# Serial_final_rev03.net
KiCad netlist of a schematic drawn in EAGLE
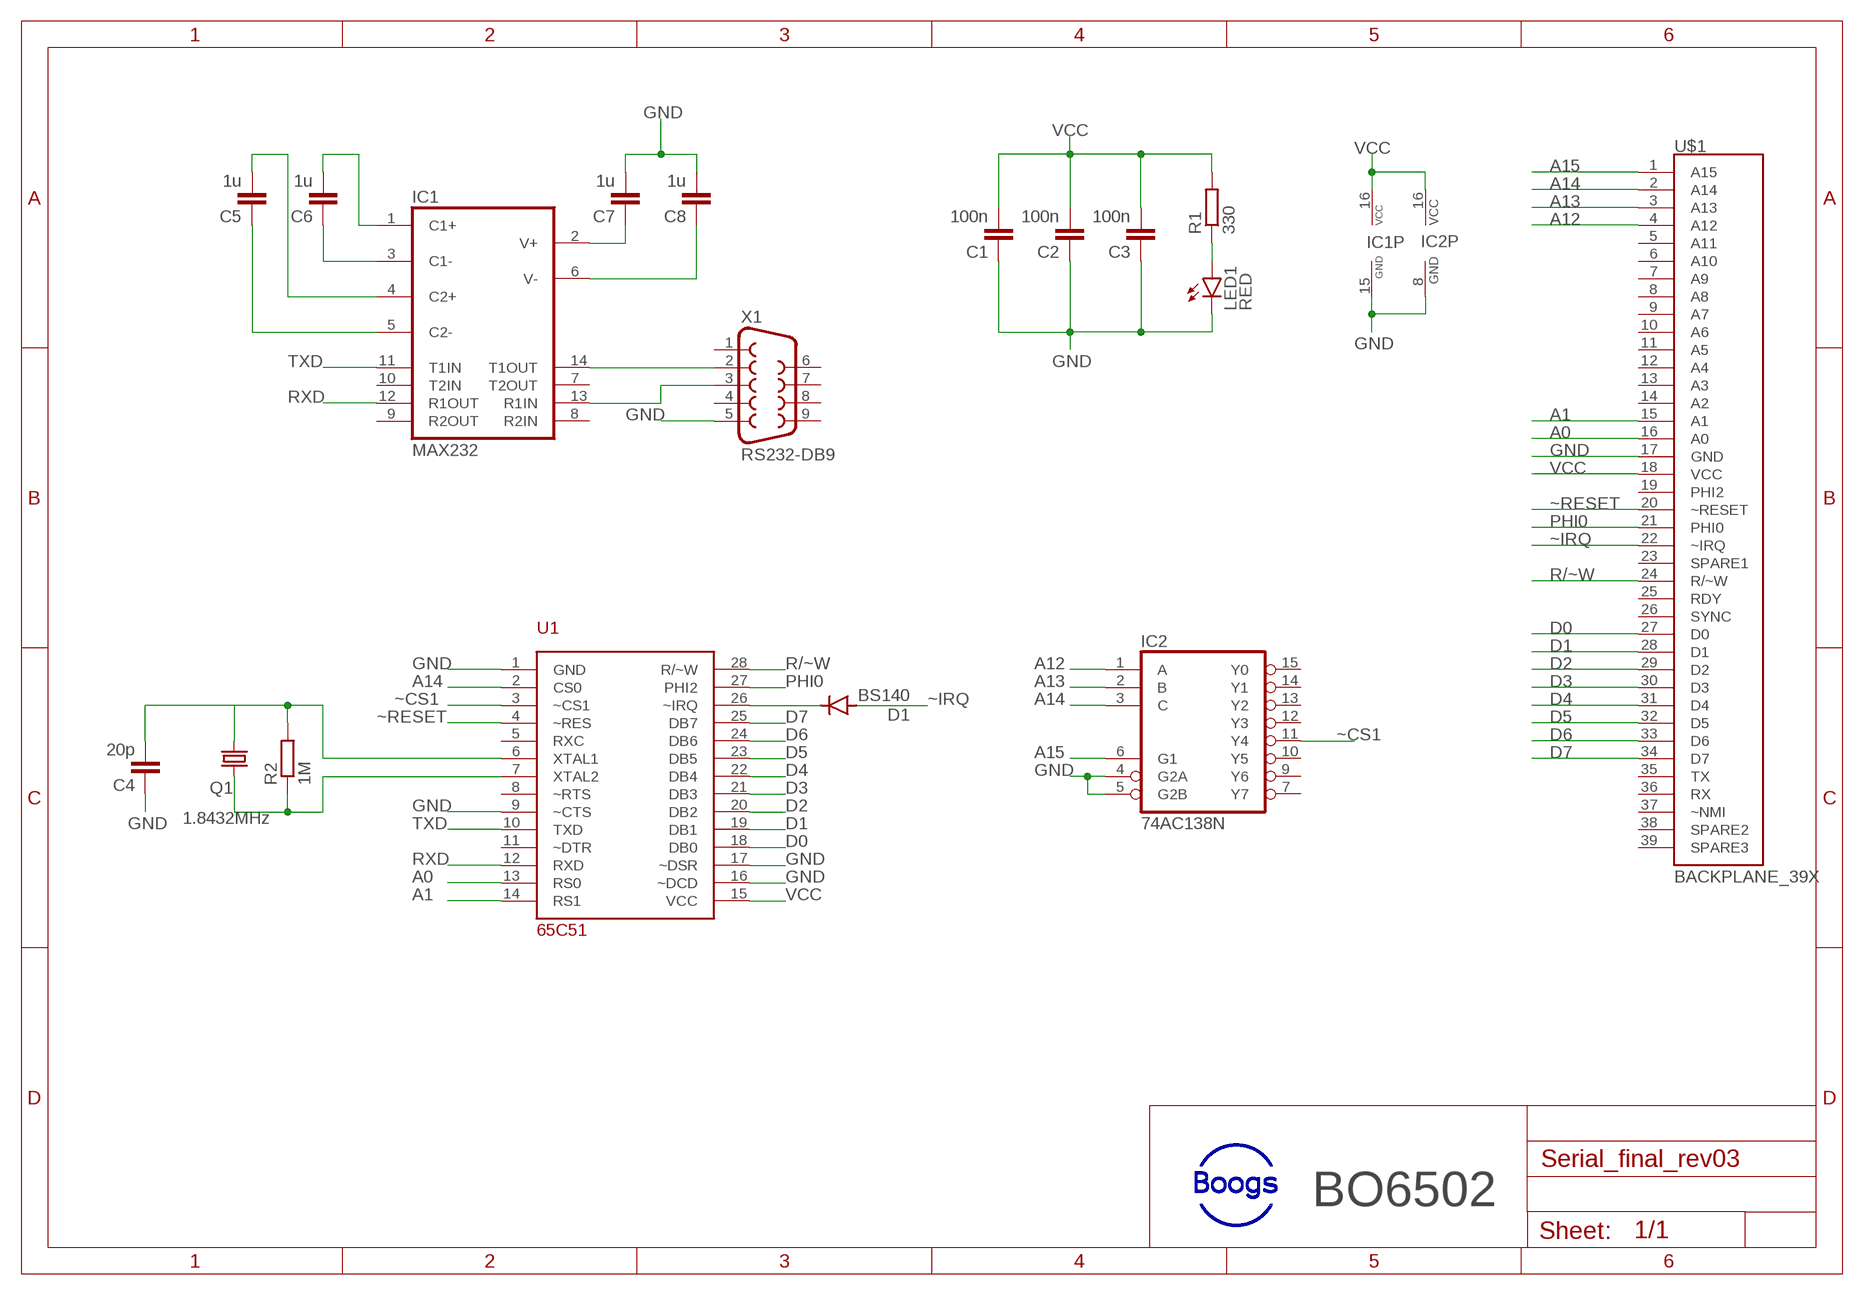
[diagram p0: schematic, sheet 1]

(export (version "E")
  (design (tool "Eeschema 10.0.6"))
  (components
    (comp (ref "C1")
      (value "100n")
      (footprint "eagle-import:C025-025X050")
      (libsource (lib "eagle-import") (part "C-EU025-025X050"))
    )
    (comp (ref "C2")
      (value "100n")
      (footprint "eagle-import:C025-025X050")
      (libsource (lib "eagle-import") (part "C-EU025-025X050"))
    )
    (comp (ref "C3")
      (value "100n")
      (footprint "eagle-import:C025-025X050")
      (libsource (lib "eagle-import") (part "C-EU025-025X050"))
    )
    (comp (ref "C4")
      (value "20p")
      (footprint "eagle-import:C025-025X050")
      (libsource (lib "eagle-import") (part "C-EU025-025X050"))
    )
    (comp (ref "C5")
      (value "1u")
      (footprint "eagle-import:C050-025X075")
      (libsource (lib "eagle-import") (part "C-EU050-025X075"))
    )
    (comp (ref "C6")
      (value "1u")
      (footprint "eagle-import:C050-025X075")
      (libsource (lib "eagle-import") (part "C-EU050-025X075"))
    )
    (comp (ref "C7")
      (value "1u")
      (footprint "eagle-import:C050-025X075")
      (libsource (lib "eagle-import") (part "C-EU050-025X075"))
    )
    (comp (ref "C8")
      (value "1u")
      (footprint "eagle-import:C050-025X075")
      (libsource (lib "eagle-import") (part "C-EU050-025X075"))
    )
    (comp (ref "D1")
      (value "BS140")
      (footprint "eagle-import:DO41-10")
      (libsource (lib "eagle-import") (part "1N4004"))
    )
    (comp (ref "IC1")
      (value "MAX232")
      (footprint "eagle-import:DIL16")
      (fields (field (name "MF") "MAXIM") (field (name "MPN") "MAX232ACPE+"))
      (libsource (lib "eagle-import") (part "MAX232"))
    )
    (comp (ref "IC2")
      (value "74AC138N")
      (footprint "eagle-import:DIL16")
      (libsource (lib "eagle-import") (part "74138NAC"))
    )
    (comp (ref "LED1")
      (value "RED")
      (footprint "eagle-import:LED5MM")
      (libsource (lib "eagle-import") (part "LED5MM"))
    )
    (comp (ref "Q1")
      (value "1.8432MHz")
      (footprint "eagle-import:HC49_S")
      (libsource (lib "eagle-import") (part "CRYSTALHC49S"))
    )
    (comp (ref "R1")
      (value "330")
      (footprint "eagle-import:0207_10")
      (libsource (lib "eagle-import") (part "R-EU_0207/10"))
    )
    (comp (ref "R2")
      (value "1M")
      (footprint "eagle-import:0207_10")
      (libsource (lib "eagle-import") (part "R-EU_0207/10"))
    )
    (comp (ref "U$1")
      (value "BACKPLANE_39X")
      (footprint "eagle-import:BP_39X")
      (fields (field (name "A15") "A15"))
      (libsource (lib "eagle-import") (part "BACKPLANE_39X"))
    )
    (comp (ref "U1")
      (value "65C51")
      (footprint "eagle-import:DIL28")
      (libsource (lib "eagle-import") (part "65C51"))
    )
    (comp (ref "X1")
      (value "RS232-DB9")
      (footprint "eagle-import:F09HP")
      (libsource (lib "eagle-import") (part "F09HP"))
    )
  )
  (nets
    (net (code "1") (name "/A0") (class "Default")
      (node (ref "U$1") (pin "16") (pinfunction "A0_16") (pintype "bidirectional"))
      (node (ref "U1") (pin "13") (pinfunction "RS0_13") (pintype "bidirectional"))
    )
    (net (code "2") (name "/A1") (class "Default")
      (node (ref "U$1") (pin "15") (pinfunction "A1_15") (pintype "bidirectional"))
      (node (ref "U1") (pin "14") (pinfunction "RS1_14") (pintype "bidirectional"))
    )
    (net (code "3") (name "/A12") (class "Default")
      (node (ref "IC2") (pin "1") (pinfunction "A_1") (pintype "input"))
      (node (ref "U$1") (pin "4") (pinfunction "A12_4") (pintype "bidirectional"))
    )
    (net (code "4") (name "/A13") (class "Default")
      (node (ref "IC2") (pin "2") (pinfunction "B_2") (pintype "input"))
      (node (ref "U$1") (pin "3") (pinfunction "A13_3") (pintype "bidirectional"))
    )
    (net (code "5") (name "/A14") (class "Default")
      (node (ref "IC2") (pin "3") (pinfunction "C_3") (pintype "input"))
      (node (ref "U$1") (pin "2") (pinfunction "A14_2") (pintype "bidirectional"))
      (node (ref "U1") (pin "2") (pinfunction "CS0_2") (pintype "bidirectional"))
    )
    (net (code "6") (name "/A15") (class "Default")
      (node (ref "IC2") (pin "6") (pinfunction "G1_6") (pintype "input"))
      (node (ref "U$1") (pin "1") (pinfunction "A15_1") (pintype "bidirectional"))
    )
    (net (code "7") (name "/D0") (class "Default")
      (node (ref "U$1") (pin "27") (pinfunction "D0_27") (pintype "bidirectional"))
      (node (ref "U1") (pin "18") (pinfunction "DB0_18") (pintype "bidirectional"))
    )
    (net (code "8") (name "/D1") (class "Default")
      (node (ref "U$1") (pin "28") (pinfunction "D1_28") (pintype "bidirectional"))
      (node (ref "U1") (pin "19") (pinfunction "DB1_19") (pintype "bidirectional"))
    )
    (net (code "9") (name "/D2") (class "Default")
      (node (ref "U$1") (pin "29") (pinfunction "D2_29") (pintype "bidirectional"))
      (node (ref "U1") (pin "20") (pinfunction "DB2_20") (pintype "bidirectional"))
    )
    (net (code "10") (name "/D3") (class "Default")
      (node (ref "U$1") (pin "30") (pinfunction "D3_30") (pintype "bidirectional"))
      (node (ref "U1") (pin "21") (pinfunction "DB3_21") (pintype "bidirectional"))
    )
    (net (code "11") (name "/D4") (class "Default")
      (node (ref "U$1") (pin "31") (pinfunction "D4_31") (pintype "bidirectional"))
      (node (ref "U1") (pin "22") (pinfunction "DB4_22") (pintype "bidirectional"))
    )
    (net (code "12") (name "/D5") (class "Default")
      (node (ref "U$1") (pin "32") (pinfunction "D5_32") (pintype "bidirectional"))
      (node (ref "U1") (pin "23") (pinfunction "DB5_23") (pintype "bidirectional"))
    )
    (net (code "13") (name "/D6") (class "Default")
      (node (ref "U$1") (pin "33") (pinfunction "D6_33") (pintype "bidirectional"))
      (node (ref "U1") (pin "24") (pinfunction "DB6_24") (pintype "bidirectional"))
    )
    (net (code "14") (name "/D7") (class "Default")
      (node (ref "U$1") (pin "34") (pinfunction "D7_34") (pintype "bidirectional"))
      (node (ref "U1") (pin "25") (pinfunction "DB7_25") (pintype "bidirectional"))
    )
    (net (code "15") (name "/GND") (class "Default")
      (node (ref "C1") (pin "1") (pinfunction "1_1") (pintype "passive"))
      (node (ref "C2") (pin "1") (pinfunction "1_1") (pintype "passive"))
      (node (ref "C3") (pin "1") (pinfunction "1_1") (pintype "passive"))
      (node (ref "C4") (pin "1") (pinfunction "1_1") (pintype "passive"))
      (node (ref "C7") (pin "2") (pinfunction "2_2") (pintype "passive"))
      (node (ref "C8") (pin "2") (pinfunction "2_2") (pintype "passive"))
      (node (ref "IC1") (pin "15") (pinfunction "GND_15") (pintype "power_in"))
      (node (ref "IC2") (pin "4") (pinfunction "G2A_4") (pintype "input"))
      (node (ref "IC2") (pin "5") (pinfunction "G2B_5") (pintype "input"))
      (node (ref "IC2") (pin "8") (pinfunction "GND_8") (pintype "power_in"))
      (node (ref "LED1") (pin "K") (pinfunction "C_K") (pintype "passive"))
      (node (ref "U$1") (pin "17") (pinfunction "GND_17") (pintype "bidirectional"))
      (node (ref "U1") (pin "1") (pinfunction "GND_1") (pintype "bidirectional"))
      (node (ref "U1") (pin "16") (pinfunction "~{DCD}_16") (pintype "bidirectional"))
      (node (ref "U1") (pin "17") (pinfunction "~{DSR}_17") (pintype "bidirectional"))
      (node (ref "U1") (pin "9") (pinfunction "~{CTS}_9") (pintype "bidirectional"))
      (node (ref "X1") (pin "5") (pinfunction "5_5") (pintype "passive"))
    )
    (net (code "16") (name "/PHI0") (class "Default")
      (node (ref "U$1") (pin "21") (pinfunction "PHI0_21") (pintype "bidirectional"))
      (node (ref "U1") (pin "27") (pinfunction "PHI2_27") (pintype "bidirectional"))
    )
    (net (code "17") (name "/RXD") (class "Default")
      (node (ref "IC1") (pin "12") (pinfunction "R1OUT_12") (pintype "output"))
      (node (ref "U1") (pin "12") (pinfunction "RXD_12") (pintype "bidirectional"))
    )
    (net (code "18") (name "/R{slash}~{W}") (class "Default")
      (node (ref "U$1") (pin "24") (pinfunction "R/~{W}_24") (pintype "bidirectional"))
      (node (ref "U1") (pin "28") (pinfunction "R/~{W}_28") (pintype "bidirectional"))
    )
    (net (code "19") (name "/TXD") (class "Default")
      (node (ref "IC1") (pin "11") (pinfunction "T1IN_11") (pintype "input"))
      (node (ref "U1") (pin "10") (pinfunction "TXD_10") (pintype "bidirectional"))
    )
    (net (code "20") (name "/VCC") (class "Default")
      (node (ref "C1") (pin "2") (pinfunction "2_2") (pintype "passive"))
      (node (ref "C2") (pin "2") (pinfunction "2_2") (pintype "passive"))
      (node (ref "C3") (pin "2") (pinfunction "2_2") (pintype "passive"))
      (node (ref "IC1") (pin "16") (pinfunction "VCC_16") (pintype "power_in"))
      (node (ref "IC2") (pin "16") (pinfunction "VCC_16") (pintype "power_in"))
      (node (ref "R1") (pin "2") (pinfunction "2_2") (pintype "passive"))
      (node (ref "U$1") (pin "18") (pinfunction "VCC_18") (pintype "bidirectional"))
      (node (ref "U1") (pin "15") (pinfunction "VCC_15") (pintype "bidirectional"))
    )
    (net (code "21") (name "/~{CS1}") (class "Default")
      (node (ref "IC2") (pin "11") (pinfunction "Y4_11") (pintype "output"))
      (node (ref "U1") (pin "3") (pinfunction "~{CS1}_3") (pintype "bidirectional"))
    )
    (net (code "22") (name "/~{IRQ}") (class "Default")
      (node (ref "D1") (pin "A") (pinfunction "A_A") (pintype "passive"))
      (node (ref "U$1") (pin "22") (pinfunction "~{IRQ}_22") (pintype "bidirectional"))
    )
    (net (code "23") (name "/~{RESET}") (class "Default")
      (node (ref "U$1") (pin "20") (pinfunction "~{RESET}_20") (pintype "bidirectional"))
      (node (ref "U1") (pin "4") (pinfunction "~{RES}_4") (pintype "bidirectional"))
    )
    (net (code "24") (name "Net-(IC1A-C1+)") (class "Default")
      (node (ref "C6") (pin "2") (pinfunction "2_2") (pintype "passive"))
      (node (ref "IC1") (pin "1") (pinfunction "C1+_1") (pintype "bidirectional"))
    )
    (net (code "25") (name "Net-(IC1A-C1-)") (class "Default")
      (node (ref "C6") (pin "1") (pinfunction "1_1") (pintype "passive"))
      (node (ref "IC1") (pin "3") (pinfunction "C1-_3") (pintype "bidirectional"))
    )
    (net (code "26") (name "Net-(IC1A-C2+)") (class "Default")
      (node (ref "C5") (pin "2") (pinfunction "2_2") (pintype "passive"))
      (node (ref "IC1") (pin "4") (pinfunction "C2+_4") (pintype "bidirectional"))
    )
    (net (code "27") (name "Net-(IC1A-C2-)") (class "Default")
      (node (ref "C5") (pin "1") (pinfunction "1_1") (pintype "passive"))
      (node (ref "IC1") (pin "5") (pinfunction "C2-_5") (pintype "bidirectional"))
    )
    (net (code "28") (name "Net-(IC1A-R1IN)") (class "Default")
      (node (ref "IC1") (pin "13") (pinfunction "R1IN_13") (pintype "input"))
      (node (ref "X1") (pin "3") (pinfunction "3_3") (pintype "passive"))
    )
    (net (code "29") (name "Net-(IC1A-T1OUT)") (class "Default")
      (node (ref "IC1") (pin "14") (pinfunction "T1OUT_14") (pintype "output"))
      (node (ref "X1") (pin "2") (pinfunction "2_2") (pintype "passive"))
    )
    (net (code "30") (name "Net-(IC1A-V+)") (class "Default")
      (node (ref "C7") (pin "1") (pinfunction "1_1") (pintype "passive"))
      (node (ref "IC1") (pin "2") (pinfunction "V+_2") (pintype "bidirectional"))
    )
    (net (code "31") (name "Net-(IC1A-V-)") (class "Default")
      (node (ref "C8") (pin "1") (pinfunction "1_1") (pintype "passive"))
      (node (ref "IC1") (pin "6") (pinfunction "V-_6") (pintype "bidirectional"))
    )
    (net (code "32") (name "Net-(LED1-PadA)") (class "Default")
      (node (ref "LED1") (pin "A") (pinfunction "A_A") (pintype "passive"))
      (node (ref "R1") (pin "1") (pinfunction "1_1") (pintype "passive"))
    )
    (net (code "33") (name "Net-(U1-XTAL1)") (class "Default")
      (node (ref "C4") (pin "2") (pinfunction "2_2") (pintype "passive"))
      (node (ref "Q1") (pin "2") (pinfunction "2_2") (pintype "passive"))
      (node (ref "R2") (pin "2") (pinfunction "2_2") (pintype "passive"))
      (node (ref "U1") (pin "6") (pinfunction "XTAL1_6") (pintype "bidirectional"))
    )
    (net (code "34") (name "Net-(U1-XTAL2)") (class "Default")
      (node (ref "Q1") (pin "1") (pinfunction "1_1") (pintype "passive"))
      (node (ref "R2") (pin "1") (pinfunction "1_1") (pintype "passive"))
      (node (ref "U1") (pin "7") (pinfunction "XTAL2_7") (pintype "bidirectional"))
    )
    (net (code "35") (name "Net-(U1-~{IRQ})") (class "Default")
      (node (ref "D1") (pin "C") (pinfunction "C_C") (pintype "passive"))
      (node (ref "U1") (pin "26") (pinfunction "~{IRQ}_26") (pintype "bidirectional"))
    )
    (net (code "36") (name "unconnected-(IC1A-R2IN-Pad8)") (class "Default")
      (node (ref "IC1") (pin "8") (pinfunction "R2IN_8") (pintype "input"))
    )
    (net (code "37") (name "unconnected-(IC1A-R2OUT-Pad9)") (class "Default")
      (node (ref "IC1") (pin "9") (pinfunction "R2OUT_9") (pintype "output"))
    )
    (net (code "38") (name "unconnected-(IC1A-T2IN-Pad10)") (class "Default")
      (node (ref "IC1") (pin "10") (pinfunction "T2IN_10") (pintype "input"))
    )
    (net (code "39") (name "unconnected-(IC1A-T2OUT-Pad7)") (class "Default")
      (node (ref "IC1") (pin "7") (pinfunction "T2OUT_7") (pintype "output"))
    )
    (net (code "40") (name "unconnected-(IC2A-Y0-Pad15)") (class "Default")
      (node (ref "IC2") (pin "15") (pinfunction "Y0_15") (pintype "output"))
    )
    (net (code "41") (name "unconnected-(IC2A-Y1-Pad14)") (class "Default")
      (node (ref "IC2") (pin "14") (pinfunction "Y1_14") (pintype "output"))
    )
    (net (code "42") (name "unconnected-(IC2A-Y2-Pad13)") (class "Default")
      (node (ref "IC2") (pin "13") (pinfunction "Y2_13") (pintype "output"))
    )
    (net (code "43") (name "unconnected-(IC2A-Y3-Pad12)") (class "Default")
      (node (ref "IC2") (pin "12") (pinfunction "Y3_12") (pintype "output"))
    )
    (net (code "44") (name "unconnected-(IC2A-Y5-Pad10)") (class "Default")
      (node (ref "IC2") (pin "10") (pinfunction "Y5_10") (pintype "output"))
    )
    (net (code "45") (name "unconnected-(IC2A-Y6-Pad9)") (class "Default")
      (node (ref "IC2") (pin "9") (pinfunction "Y6_9") (pintype "output"))
    )
    (net (code "46") (name "unconnected-(IC2A-Y7-Pad7)") (class "Default")
      (node (ref "IC2") (pin "7") (pinfunction "Y7_7") (pintype "output"))
    )
    (net (code "47") (name "unconnected-(U$1-A2-Pad14)") (class "Default")
      (node (ref "U$1") (pin "14") (pinfunction "A2_14") (pintype "bidirectional"))
    )
    (net (code "48") (name "unconnected-(U$1-A3-Pad13)") (class "Default")
      (node (ref "U$1") (pin "13") (pinfunction "A3_13") (pintype "bidirectional"))
    )
    (net (code "49") (name "unconnected-(U$1-A4-Pad12)") (class "Default")
      (node (ref "U$1") (pin "12") (pinfunction "A4_12") (pintype "bidirectional"))
    )
    (net (code "50") (name "unconnected-(U$1-A5-Pad11)") (class "Default")
      (node (ref "U$1") (pin "11") (pinfunction "A5_11") (pintype "bidirectional"))
    )
    (net (code "51") (name "unconnected-(U$1-A6-Pad10)") (class "Default")
      (node (ref "U$1") (pin "10") (pinfunction "A6_10") (pintype "bidirectional"))
    )
    (net (code "52") (name "unconnected-(U$1-A7-Pad9)") (class "Default")
      (node (ref "U$1") (pin "9") (pinfunction "A7_9") (pintype "bidirectional"))
    )
    (net (code "53") (name "unconnected-(U$1-A8-Pad8)") (class "Default")
      (node (ref "U$1") (pin "8") (pinfunction "A8_8") (pintype "bidirectional"))
    )
    (net (code "54") (name "unconnected-(U$1-A9-Pad7)") (class "Default")
      (node (ref "U$1") (pin "7") (pinfunction "A9_7") (pintype "bidirectional"))
    )
    (net (code "55") (name "unconnected-(U$1-A10-Pad6)") (class "Default")
      (node (ref "U$1") (pin "6") (pinfunction "A10_6") (pintype "bidirectional"))
    )
    (net (code "56") (name "unconnected-(U$1-A11-Pad5)") (class "Default")
      (node (ref "U$1") (pin "5") (pinfunction "A11_5") (pintype "bidirectional"))
    )
    (net (code "57") (name "unconnected-(U$1-PHI2-Pad19)") (class "Default")
      (node (ref "U$1") (pin "19") (pinfunction "PHI2_19") (pintype "bidirectional"))
    )
    (net (code "58") (name "unconnected-(U$1-RDY-Pad25)") (class "Default")
      (node (ref "U$1") (pin "25") (pinfunction "RDY_25") (pintype "bidirectional"))
    )
    (net (code "59") (name "unconnected-(U$1-RX-Pad36)") (class "Default")
      (node (ref "U$1") (pin "36") (pinfunction "RX_36") (pintype "bidirectional"))
    )
    (net (code "60") (name "unconnected-(U$1-SPARE1-Pad23)") (class "Default")
      (node (ref "U$1") (pin "23") (pinfunction "SPARE1_23") (pintype "bidirectional"))
    )
    (net (code "61") (name "unconnected-(U$1-SPARE2-Pad38)") (class "Default")
      (node (ref "U$1") (pin "38") (pinfunction "SPARE2_38") (pintype "bidirectional"))
    )
    (net (code "62") (name "unconnected-(U$1-SPARE3-Pad39)") (class "Default")
      (node (ref "U$1") (pin "39") (pinfunction "SPARE3_39") (pintype "bidirectional"))
    )
    (net (code "63") (name "unconnected-(U$1-SYNC-Pad26)") (class "Default")
      (node (ref "U$1") (pin "26") (pinfunction "SYNC_26") (pintype "bidirectional"))
    )
    (net (code "64") (name "unconnected-(U$1-TX-Pad35)") (class "Default")
      (node (ref "U$1") (pin "35") (pinfunction "TX_35") (pintype "bidirectional"))
    )
    (net (code "65") (name "unconnected-(U$1-~{NMI}-Pad37)") (class "Default")
      (node (ref "U$1") (pin "37") (pinfunction "~{NMI}_37") (pintype "bidirectional"))
    )
    (net (code "66") (name "unconnected-(U1-RXC-Pad5)") (class "Default")
      (node (ref "U1") (pin "5") (pinfunction "RXC_5") (pintype "bidirectional"))
    )
    (net (code "67") (name "unconnected-(U1-~{DTR}-Pad11)") (class "Default")
      (node (ref "U1") (pin "11") (pinfunction "~{DTR}_11") (pintype "bidirectional"))
    )
    (net (code "68") (name "unconnected-(U1-~{RTS}-Pad8)") (class "Default")
      (node (ref "U1") (pin "8") (pinfunction "~{RTS}_8") (pintype "bidirectional"))
    )
    (net (code "69") (name "unconnected-(X1-Pad1)") (class "Default")
      (node (ref "X1") (pin "1") (pinfunction "1_1") (pintype "passive"))
    )
    (net (code "70") (name "unconnected-(X1-Pad4)") (class "Default")
      (node (ref "X1") (pin "4") (pinfunction "4_4") (pintype "passive"))
    )
    (net (code "71") (name "unconnected-(X1-Pad6)") (class "Default")
      (node (ref "X1") (pin "6") (pinfunction "6_6") (pintype "passive"))
    )
    (net (code "72") (name "unconnected-(X1-Pad7)") (class "Default")
      (node (ref "X1") (pin "7") (pinfunction "7_7") (pintype "passive"))
    )
    (net (code "73") (name "unconnected-(X1-Pad8)") (class "Default")
      (node (ref "X1") (pin "8") (pinfunction "8_8") (pintype "passive"))
    )
    (net (code "74") (name "unconnected-(X1-Pad9)") (class "Default")
      (node (ref "X1") (pin "9") (pinfunction "9_9") (pintype "passive"))
    )
  )
)
